# lcd13264-module.net
KiCad netlist of a schematic drawn in EAGLE
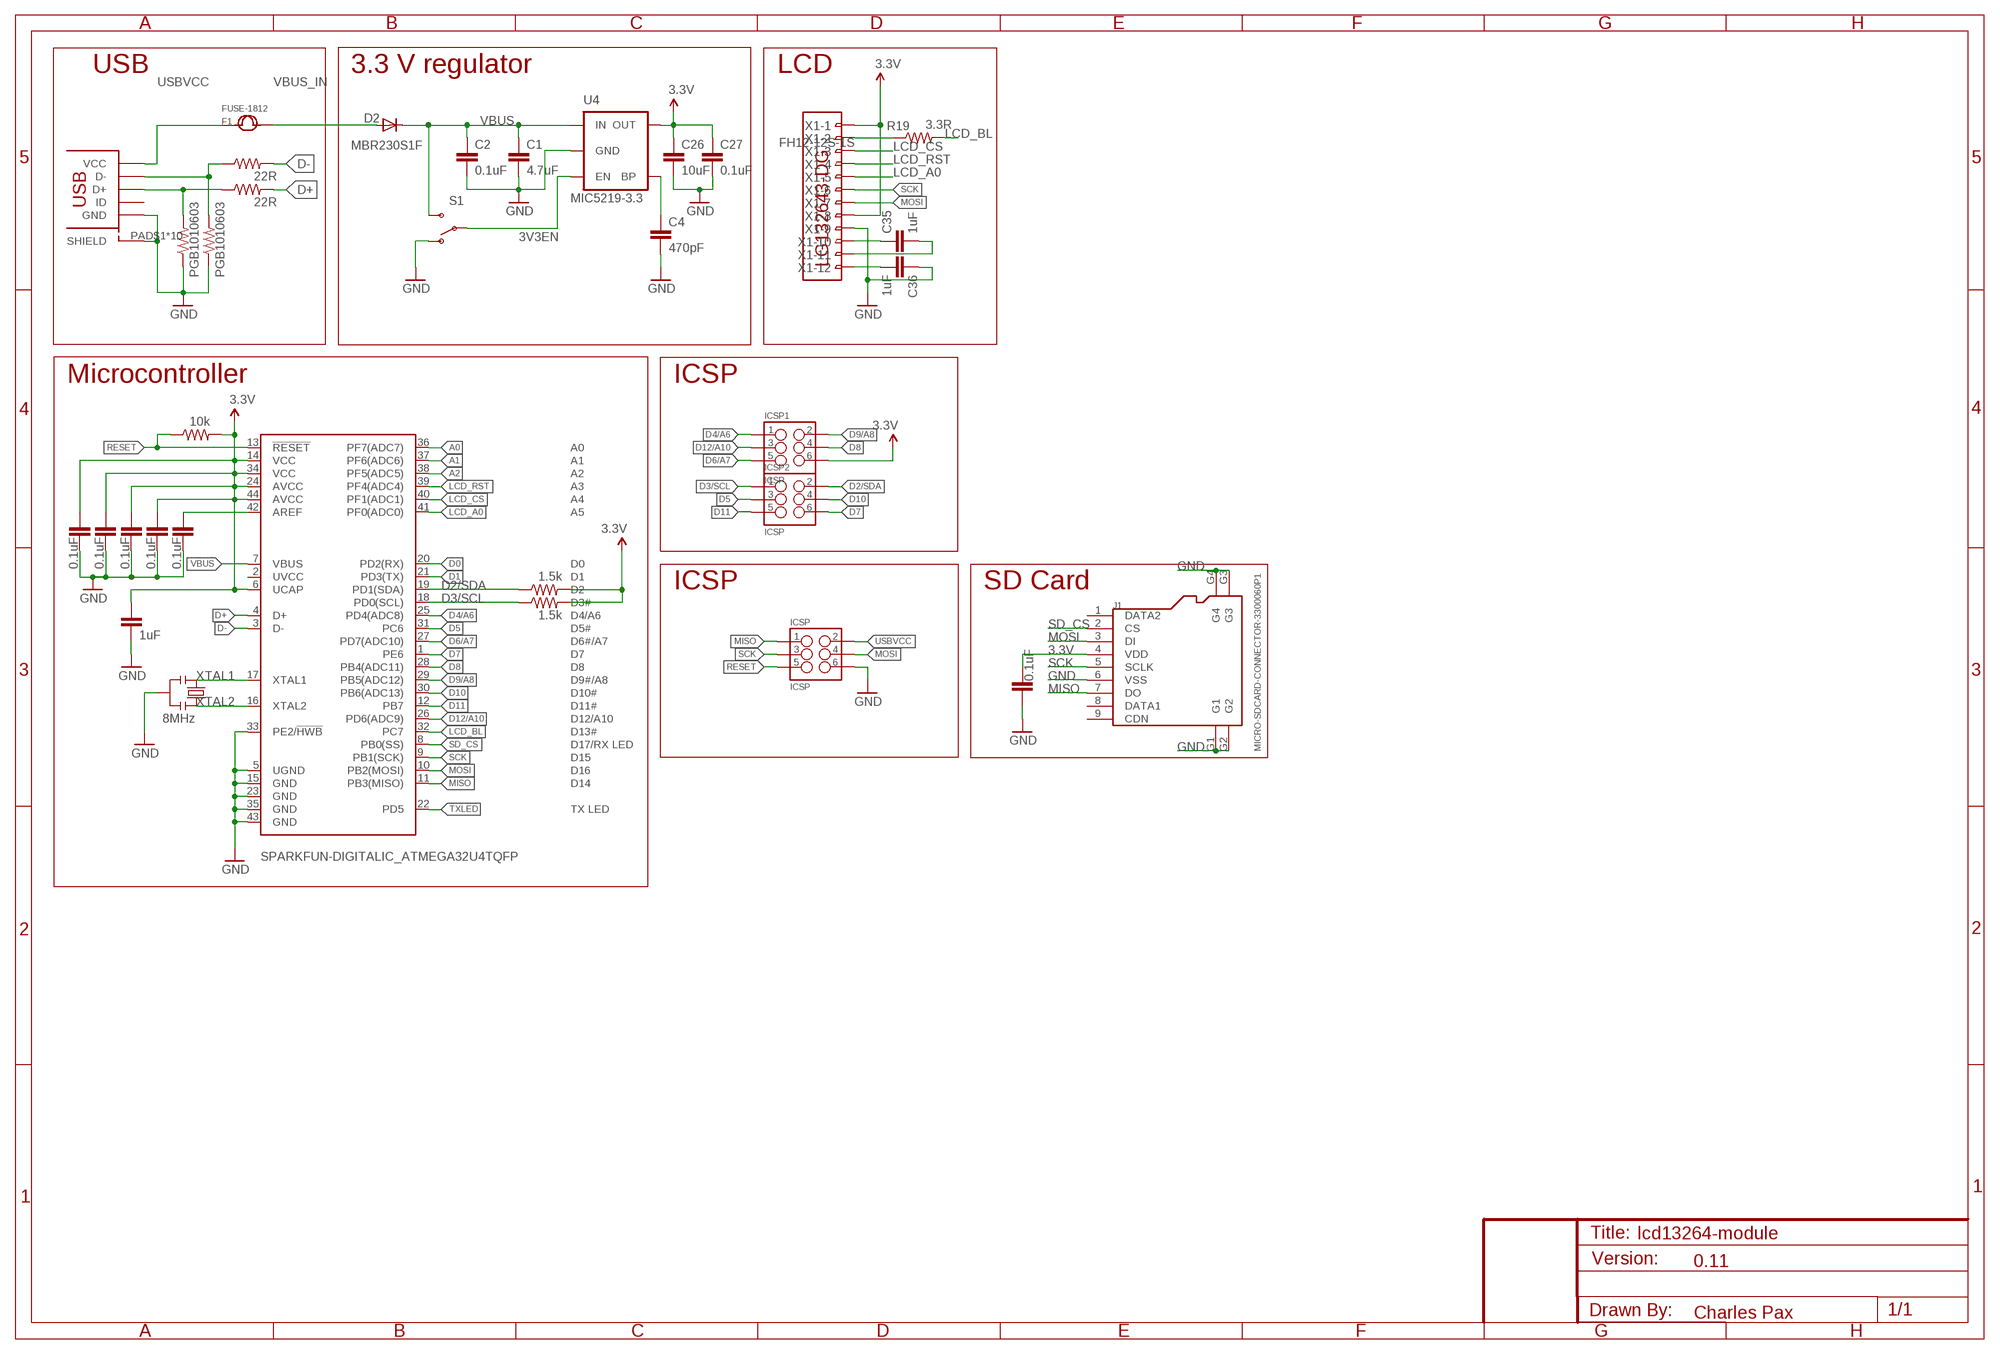
[diagram p0: schematic, sheet 1]

(export (version "E")
  (design (tool "Eeschema 10.0.6"))
  (components
    (comp (ref "C1")
      (value "4.7uF")
      (footprint "eagle-import:SPARKFUN-CAPACITORS_0603-CAP")
      (fields (field (name "MPN") "GRM188R60J475KE19D"))
      (libsource (lib "eagle-import") (part "SPARKFUN-CAPACITORS_CAP0603-CAP"))
    )
    (comp (ref "C2")
      (value "0.1uF")
      (footprint "eagle-import:SPARKFUN-CAPACITORS_0603-CAP")
      (fields (field (name "MPN") "CL10B104KO8NNNC"))
      (libsource (lib "eagle-import") (part "SPARKFUN-CAPACITORS_CAP0603-CAP"))
    )
    (comp (ref "C3")
      (value "0.1uF")
      (footprint "eagle-import:SPARKFUN-CAPACITORS_0603-CAP")
      (fields (field (name "MPN") "CL10B104KO8NNNC"))
      (libsource (lib "eagle-import") (part "SPARKFUN-CAPACITORS_CAP0603-CAP"))
    )
    (comp (ref "C4")
      (value "470pF")
      (footprint "eagle-import:SPARKFUN-CAPACITORS_0603-CAP")
      (fields (field (name "MPN") "C1608X5R1A474K080AA"))
      (libsource (lib "eagle-import") (part "SPARKFUN-CAPACITORS_CAP0603-CAP"))
    )
    (comp (ref "C5")
      (value "0.1uF")
      (footprint "eagle-import:SPARKFUN-CAPACITORS_0603-CAP")
      (fields (field (name "MPN") "CL10B104KO8NNNC"))
      (libsource (lib "eagle-import") (part "SPARKFUN-CAPACITORS_CAP0603-CAP"))
    )
    (comp (ref "C19")
      (value "1uF")
      (footprint "eagle-import:SPARKFUN-CAPACITORS_0603-CAP")
      (fields (field (name "MPN") "LMK107B7105KA-T"))
      (libsource (lib "eagle-import") (part "SPARKFUN-CAPACITORS_CAP0603-CAP"))
    )
    (comp (ref "C21")
      (value "0.1uF")
      (footprint "eagle-import:SPARKFUN-CAPACITORS_0603-CAP")
      (fields (field (name "MPN") "CL10B104KO8NNNC"))
      (libsource (lib "eagle-import") (part "SPARKFUN-CAPACITORS_CAP0603-CAP"))
    )
    (comp (ref "C26")
      (value "10uF")
      (footprint "eagle-import:SPARKFUN-CAPACITORS_0603-CAP")
      (fields (field (name "MPN") "JMK107ABJ106MAHT"))
      (libsource (lib "eagle-import") (part "SPARKFUN-CAPACITORS_CAP0603-CAP"))
    )
    (comp (ref "C27")
      (value "0.1uF")
      (footprint "eagle-import:SPARKFUN-CAPACITORS_0603-CAP")
      (fields (field (name "MPN") "CL10B104KO8NNNC"))
      (libsource (lib "eagle-import") (part "SPARKFUN-CAPACITORS_CAP0603-CAP"))
    )
    (comp (ref "C32")
      (value "0.1uF")
      (footprint "eagle-import:SPARKFUN-CAPACITORS_0603-CAP")
      (fields (field (name "MPN") "CL10B104KO8NNNC"))
      (libsource (lib "eagle-import") (part "SPARKFUN-CAPACITORS_CAP0603-CAP"))
    )
    (comp (ref "C33")
      (value "0.1uF")
      (footprint "eagle-import:SPARKFUN-CAPACITORS_0603-CAP")
      (fields (field (name "MPN") "CL10B104KO8NNNC"))
      (libsource (lib "eagle-import") (part "SPARKFUN-CAPACITORS_CAP0603-CAP"))
    )
    (comp (ref "C34")
      (value "0.1uF")
      (footprint "eagle-import:SPARKFUN-CAPACITORS_0603-CAP")
      (fields (field (name "MPN") "CL10B104KO8NNNC"))
      (libsource (lib "eagle-import") (part "SPARKFUN-CAPACITORS_CAP0603-CAP"))
    )
    (comp (ref "C35")
      (value "1uF")
      (footprint "eagle-import:SPARKFUN-CAPACITORS_0603-CAP")
      (fields (field (name "MPN") "LMK107B7105KA-T"))
      (libsource (lib "eagle-import") (part "SPARKFUN-CAPACITORS_CAP0603-CAP"))
    )
    (comp (ref "C36")
      (value "1uF")
      (footprint "eagle-import:SPARKFUN-CAPACITORS_0603-CAP")
      (fields (field (name "MPN") "LMK107B7105KA-T"))
      (libsource (lib "eagle-import") (part "SPARKFUN-CAPACITORS_CAP0603-CAP"))
    )
    (comp (ref "D2")
      (value "MBR230S1F")
      (footprint "eagle-import:SOD123")
      (fields (field (name "MPN") "B340A-13-F"))
      (libsource (lib "eagle-import") (part "SPARKFUN-DISCRETESEMI_DIODESOD123SOD123"))
    )
    (comp (ref "F1")
      (value "FUSE-1812")
      (footprint "eagle-import:F1812")
      (libsource (lib "eagle-import") (part "FUSE-1812"))
    )
    (comp (ref "ICSP")
      (value "ICSP")
      (footprint "eagle-import:SPARKFUN-CONNECTORS_2X3_SMT_POSTS_PAXINSTRUMENT")
      (fields (field (name "MPN") "95278-101A06LF"))
      (libsource (lib "eagle-import") (part "SPARKFUN-CONNECTORS_M03X2PAX"))
    )
    (comp (ref "ICSP1")
      (value "ICSP")
      (footprint "eagle-import:SPARKFUN-CONNECTORS_2X3_SMT_POSTS_PAXINSTRUMENT")
      (fields (field (name "MPN") "95278-101A06LF"))
      (libsource (lib "eagle-import") (part "SPARKFUN-CONNECTORS_M03X2PAX"))
    )
    (comp (ref "ICSP2")
      (value "ICSP")
      (footprint "eagle-import:SPARKFUN-CONNECTORS_2X3_SMT_POSTS_PAXINSTRUMENT")
      (fields (field (name "MPN") "95278-101A06LF"))
      (libsource (lib "eagle-import") (part "SPARKFUN-CONNECTORS_M03X2PAX"))
    )
    (comp (ref "J1")
      (value "MICRO-SDCARD-CONNECTOR-3300060P1")
      (footprint "eagle-import:9P-SMD-W-RING")
      (libsource (lib "eagle-import") (part "MICRO-SDCARD-CONNECTOR-3300060P1"))
    )
    (comp (ref "R4")
      (value "10k")
      (footprint "eagle-import:SPARKFUN-RESISTORS_0603-RES")
      (fields (field (name "MPN") "RC1608J103CS"))
      (libsource (lib "eagle-import") (part "SPARKFUN-RESISTORS_RESISTOR0603-RES"))
    )
    (comp (ref "R9")
      (value "22R")
      (footprint "eagle-import:SPARKFUN-RESISTORS_0603-RES")
      (fields (field (name "MPN") "RC0603JR-0722RL"))
      (libsource (lib "eagle-import") (part "SPARKFUN-RESISTORS_RESISTOR0603-RES"))
    )
    (comp (ref "R10")
      (value "22R")
      (footprint "eagle-import:SPARKFUN-RESISTORS_0603-RES")
      (fields (field (name "MPN") "RC0603JR-0722RL"))
      (libsource (lib "eagle-import") (part "SPARKFUN-RESISTORS_RESISTOR0603-RES"))
    )
    (comp (ref "R13")
      (value "1.5k")
      (footprint "eagle-import:SPARKFUN-RESISTORS_0603-RES")
      (fields (field (name "MPN") "RC0603JR-071K5L"))
      (libsource (lib "eagle-import") (part "SPARKFUN-RESISTORS_RESISTOR0603-RES"))
    )
    (comp (ref "R14")
      (value "1.5k")
      (footprint "eagle-import:SPARKFUN-RESISTORS_0603-RES")
      (fields (field (name "MPN") "RC0603JR-071K5L"))
      (libsource (lib "eagle-import") (part "SPARKFUN-RESISTORS_RESISTOR0603-RES"))
    )
    (comp (ref "R19")
      (value "3.3R")
      (footprint "eagle-import:SPARKFUN-RESISTORS_0603-RES")
      (libsource (lib "eagle-import") (part "SPARKFUN-RESISTORS_RESISTOR0603-RES"))
    )
    (comp (ref "S1")
      (value "SWITCH-SPDT-SMD-A")
      (footprint "eagle-import:SWITCH-SPST-SMD-A")
      (libsource (lib "eagle-import") (part "SWITCH-SPDT-SMD-A"))
    )
    (comp (ref "U$1")
      (value "USB_MICROSMT+THRUHULE")
      (footprint "eagle-import:USB_MICRO_THRUHOLE")
      (fields (field (name "MPN") "10118194-0001LF"))
      (libsource (lib "eagle-import") (part "USB_MICROSMT+THRUHULE"))
    )
    (comp (ref "U$3")
      (value "SPARKFUN-DIGITALIC_ATMEGA32U4TQFP")
      (footprint "eagle-import:SPARKFUN-DIGITALIC_SPARKFUN-DIGITALIC_TQFP44")
      (libsource (lib "eagle-import") (part "SPARKFUN-DIGITALIC_ATMEGA32U4TQFP"))
    )
    (comp (ref "U$5")
      (value "LG132643-DG")
      (footprint "eagle-import:LG132643-DG")
      (fields (field (name "MPN") "LG132643-DW"))
      (libsource (lib "eagle-import") (part "LG132643-DG"))
    )
    (comp (ref "U4")
      (value "MIC5219-3.3V")
      (footprint "eagle-import:SOT23-5")
      (fields (field (name "MPN") "MIC5219-3.3YM5 TR"))
      (libsource (lib "eagle-import") (part "V_REG_LDOSMD"))
    )
    (comp (ref "X1")
      (value "FH12-12S-1S")
      (footprint "eagle-import:FH12-12S-1SH")
      (libsource (lib "eagle-import") (part "FH12-12S-1S"))
    )
    (comp (ref "Y1")
      (value "RESONATORSMD")
      (footprint "eagle-import:RESONATOR-SMD")
      (fields (field (name "MPN") "CSTCE8M00G52-R0"))
      (libsource (lib "eagle-import") (part "RESONATORSMD"))
    )
    (comp (ref "Z1")
      (value "PGB1010603")
      (footprint "eagle-import:SPARKFUN-RESISTORS_0603-RES")
      (fields (field (name "MPN") "PGB1010603NRHF"))
      (libsource (lib "eagle-import") (part "SPARKFUN-RESISTORS_RESISTOR0603-RES"))
    )
    (comp (ref "Z2")
      (value "PGB1010603")
      (footprint "eagle-import:SPARKFUN-RESISTORS_0603-RES")
      (fields (field (name "MPN") "PGB1010603NRHF"))
      (libsource (lib "eagle-import") (part "SPARKFUN-RESISTORS_RESISTOR0603-RES"))
    )
  )
  (nets
    (net (code "1") (name "/3V3EN") (class "Default")
      (node (ref "S1") (pin "2") (pinfunction "P_2") (pintype "passive"))
      (node (ref "U4") (pin "3") (pinfunction "EN_3") (pintype "input"))
    )
    (net (code "2") (name "/VBUS_IN") (class "Default")
      (node (ref "D2") (pin "A") (pinfunction "A_A") (pintype "passive"))
      (node (ref "F1") (pin "2") (pinfunction "2_2") (pintype "bidirectional"))
    )
    (net (code "3") (name "/XTAL1") (class "Default")
      (node (ref "U$3") (pin "17") (pinfunction "XTAL1_17") (pintype "bidirectional"))
      (node (ref "Y1") (pin "1") (pinfunction "1_1") (pintype "passive"))
    )
    (net (code "4") (name "/XTAL2") (class "Default")
      (node (ref "U$3") (pin "16") (pinfunction "XTAL2_16") (pintype "bidirectional"))
      (node (ref "Y1") (pin "3") (pinfunction "3_3") (pintype "passive"))
    )
    (net (code "5") (name "3.3V") (class "Default")
      (node (ref "C19") (pin "1") (pinfunction "1_1") (pintype "passive"))
      (node (ref "C21") (pin "2") (pinfunction "2_2") (pintype "passive"))
      (node (ref "C26") (pin "1") (pinfunction "1_1") (pintype "passive"))
      (node (ref "C27") (pin "1") (pinfunction "1_1") (pintype "passive"))
      (node (ref "C32") (pin "1") (pinfunction "1_1") (pintype "passive"))
      (node (ref "C33") (pin "1") (pinfunction "1_1") (pintype "passive"))
      (node (ref "C34") (pin "1") (pinfunction "1_1") (pintype "passive"))
      (node (ref "C5") (pin "1") (pinfunction "1_1") (pintype "passive"))
      (node (ref "ICSP1") (pin "6") (pinfunction "6_6") (pintype "bidirectional"))
      (node (ref "J1") (pin "4") (pinfunction "VDD_4") (pintype "bidirectional"))
      (node (ref "R13") (pin "2") (pinfunction "2_2") (pintype "passive"))
      (node (ref "R14") (pin "2") (pinfunction "2_2") (pintype "passive"))
      (node (ref "R4") (pin "2") (pinfunction "2_2") (pintype "passive"))
      (node (ref "U$3") (pin "14") (pinfunction "VCC_14") (pintype "bidirectional"))
      (node (ref "U$3") (pin "24") (pinfunction "AVCC_24") (pintype "bidirectional"))
      (node (ref "U$3") (pin "34") (pinfunction "VCC_34") (pintype "bidirectional"))
      (node (ref "U$3") (pin "44") (pinfunction "AVCC_44") (pintype "bidirectional"))
      (node (ref "U$3") (pin "6") (pinfunction "UCAP_6") (pintype "bidirectional"))
      (node (ref "U4") (pin "5") (pinfunction "OUT_5") (pintype "passive"))
      (node (ref "X1") (pin "1") (pinfunction "1_1") (pintype "passive"))
      (node (ref "X1") (pin "8") (pinfunction "1_8") (pintype "passive"))
    )
    (net (code "6") (name "A0") (class "Default")
      (node (ref "U$3") (pin "36") (pinfunction "PF7(ADC7)_36") (pintype "bidirectional"))
    )
    (net (code "7") (name "A1") (class "Default")
      (node (ref "U$3") (pin "37") (pinfunction "PF6(ADC6)_37") (pintype "bidirectional"))
    )
    (net (code "8") (name "A2") (class "Default")
      (node (ref "U$3") (pin "38") (pinfunction "PF5(ADC5)_38") (pintype "bidirectional"))
    )
    (net (code "9") (name "D+") (class "Default")
      (node (ref "R9") (pin "2") (pinfunction "2_2") (pintype "passive"))
      (node (ref "U$3") (pin "4") (pinfunction "D+_4") (pintype "bidirectional"))
    )
    (net (code "10") (name "D-") (class "Default")
      (node (ref "R10") (pin "2") (pinfunction "2_2") (pintype "passive"))
      (node (ref "U$3") (pin "3") (pinfunction "D-_3") (pintype "bidirectional"))
    )
    (net (code "11") (name "D0") (class "Default")
      (node (ref "U$3") (pin "20") (pinfunction "PD2(RX)_20") (pintype "bidirectional"))
    )
    (net (code "12") (name "D1") (class "Default")
      (node (ref "U$3") (pin "21") (pinfunction "PD3(TX)_21") (pintype "bidirectional"))
    )
    (net (code "13") (name "D2{slash}SDA") (class "Default")
      (node (ref "ICSP2") (pin "2") (pinfunction "2_2") (pintype "bidirectional"))
      (node (ref "R13") (pin "1") (pinfunction "1_1") (pintype "passive"))
      (node (ref "U$3") (pin "19") (pinfunction "PD1(SDA)_19") (pintype "bidirectional"))
    )
    (net (code "14") (name "D3{slash}SCL") (class "Default")
      (node (ref "ICSP2") (pin "1") (pinfunction "1_1") (pintype "bidirectional"))
      (node (ref "R14") (pin "1") (pinfunction "1_1") (pintype "passive"))
      (node (ref "U$3") (pin "18") (pinfunction "PD0(SCL)_18") (pintype "bidirectional"))
    )
    (net (code "15") (name "D4{slash}A6") (class "Default")
      (node (ref "ICSP1") (pin "1") (pinfunction "1_1") (pintype "bidirectional"))
      (node (ref "U$3") (pin "25") (pinfunction "PD4(ADC8)_25") (pintype "bidirectional"))
    )
    (net (code "16") (name "D5") (class "Default")
      (node (ref "ICSP2") (pin "3") (pinfunction "3_3") (pintype "bidirectional"))
      (node (ref "U$3") (pin "31") (pinfunction "PC6_31") (pintype "bidirectional"))
    )
    (net (code "17") (name "D6{slash}A7") (class "Default")
      (node (ref "ICSP1") (pin "5") (pinfunction "5_5") (pintype "bidirectional"))
      (node (ref "U$3") (pin "27") (pinfunction "PD7(ADC10)_27") (pintype "bidirectional"))
    )
    (net (code "18") (name "D7") (class "Default")
      (node (ref "ICSP2") (pin "6") (pinfunction "6_6") (pintype "bidirectional"))
      (node (ref "U$3") (pin "1") (pinfunction "PE6_1") (pintype "bidirectional"))
    )
    (net (code "19") (name "D8") (class "Default")
      (node (ref "ICSP1") (pin "4") (pinfunction "4_4") (pintype "bidirectional"))
      (node (ref "U$3") (pin "28") (pinfunction "PB4(ADC11)_28") (pintype "bidirectional"))
    )
    (net (code "20") (name "D9{slash}A8") (class "Default")
      (node (ref "ICSP1") (pin "2") (pinfunction "2_2") (pintype "bidirectional"))
      (node (ref "U$3") (pin "29") (pinfunction "PB5(ADC12)_29") (pintype "bidirectional"))
    )
    (net (code "21") (name "D10") (class "Default")
      (node (ref "ICSP2") (pin "4") (pinfunction "4_4") (pintype "bidirectional"))
      (node (ref "U$3") (pin "30") (pinfunction "PB6(ADC13)_30") (pintype "bidirectional"))
    )
    (net (code "22") (name "D11") (class "Default")
      (node (ref "ICSP2") (pin "5") (pinfunction "5_5") (pintype "bidirectional"))
      (node (ref "U$3") (pin "12") (pinfunction "PB7_12") (pintype "bidirectional"))
    )
    (net (code "23") (name "D12{slash}A10") (class "Default")
      (node (ref "ICSP1") (pin "3") (pinfunction "3_3") (pintype "bidirectional"))
      (node (ref "U$3") (pin "26") (pinfunction "PD6(ADC9)_26") (pintype "bidirectional"))
    )
    (net (code "24") (name "GND") (class "Default")
      (node (ref "C1") (pin "2") (pinfunction "2_2") (pintype "passive"))
      (node (ref "C19") (pin "2") (pinfunction "2_2") (pintype "passive"))
      (node (ref "C2") (pin "2") (pinfunction "2_2") (pintype "passive"))
      (node (ref "C21") (pin "1") (pinfunction "1_1") (pintype "passive"))
      (node (ref "C26") (pin "2") (pinfunction "2_2") (pintype "passive"))
      (node (ref "C27") (pin "2") (pinfunction "2_2") (pintype "passive"))
      (node (ref "C3") (pin "2") (pinfunction "2_2") (pintype "passive"))
      (node (ref "C32") (pin "2") (pinfunction "2_2") (pintype "passive"))
      (node (ref "C33") (pin "2") (pinfunction "2_2") (pintype "passive"))
      (node (ref "C34") (pin "2") (pinfunction "2_2") (pintype "passive"))
      (node (ref "C36") (pin "1") (pinfunction "1_1") (pintype "passive"))
      (node (ref "C4") (pin "2") (pinfunction "2_2") (pintype "passive"))
      (node (ref "C5") (pin "2") (pinfunction "2_2") (pintype "passive"))
      (node (ref "ICSP") (pin "6") (pinfunction "6_6") (pintype "bidirectional"))
      (node (ref "J1") (pin "6") (pinfunction "VSS_6") (pintype "bidirectional"))
      (node (ref "J1") (pin "G1") (pinfunction "G1_G1") (pintype "bidirectional"))
      (node (ref "J1") (pin "G2") (pinfunction "G2_G2") (pintype "bidirectional"))
      (node (ref "J1") (pin "G3") (pinfunction "G3_G3") (pintype "bidirectional"))
      (node (ref "J1") (pin "G4") (pinfunction "G4_G4") (pintype "bidirectional"))
      (node (ref "S1") (pin "1") (pinfunction "O_1") (pintype "passive"))
      (node (ref "U$1") (pin "PAD$1") (pinfunction "SHIELD_PAD$1") (pintype "bidirectional"))
      (node (ref "U$1") (pin "PAD$10") (pinfunction "SHIELD_PAD$10") (pintype "bidirectional"))
      (node (ref "U$1") (pin "PAD$2") (pinfunction "SHIELD_PAD$2") (pintype "bidirectional"))
      (node (ref "U$1") (pin "PAD$3") (pinfunction "SHIELD_PAD$3") (pintype "bidirectional"))
      (node (ref "U$1") (pin "PAD$4") (pinfunction "SHIELD_PAD$4") (pintype "bidirectional"))
      (node (ref "U$1") (pin "PAD$5") (pinfunction "SHIELD_PAD$5") (pintype "bidirectional"))
      (node (ref "U$1") (pin "PAD$6") (pinfunction "SHIELD_PAD$6") (pintype "bidirectional"))
      (node (ref "U$1") (pin "PAD$7") (pinfunction "SHIELD_PAD$7") (pintype "bidirectional"))
      (node (ref "U$1") (pin "PAD$8") (pinfunction "SHIELD_PAD$8") (pintype "bidirectional"))
      (node (ref "U$1") (pin "PAD$9") (pinfunction "SHIELD_PAD$9") (pintype "bidirectional"))
      (node (ref "U$1") (pin "PIN$5") (pinfunction "GND_PIN$5") (pintype "bidirectional"))
      (node (ref "U$3") (pin "15") (pinfunction "GND_15") (pintype "bidirectional"))
      (node (ref "U$3") (pin "23") (pinfunction "GND_23") (pintype "bidirectional"))
      (node (ref "U$3") (pin "33") (pinfunction "PE2/~{HWB}_33") (pintype "bidirectional"))
      (node (ref "U$3") (pin "35") (pinfunction "GND_35") (pintype "bidirectional"))
      (node (ref "U$3") (pin "43") (pinfunction "GND_43") (pintype "bidirectional"))
      (node (ref "U$3") (pin "5") (pinfunction "UGND_5") (pintype "bidirectional"))
      (node (ref "U4") (pin "2") (pinfunction "GND_2") (pintype "input"))
      (node (ref "X1") (pin "9") (pinfunction "1_9") (pintype "passive"))
      (node (ref "Y1") (pin "2") (pinfunction "2_2") (pintype "passive"))
      (node (ref "Z1") (pin "1") (pinfunction "1_1") (pintype "passive"))
      (node (ref "Z2") (pin "1") (pinfunction "1_1") (pintype "passive"))
    )
    (net (code "25") (name "LCD_A0") (class "Default")
      (node (ref "U$3") (pin "41") (pinfunction "PF0(ADC0)_41") (pintype "bidirectional"))
      (node (ref "X1") (pin "5") (pinfunction "1_5") (pintype "passive"))
    )
    (net (code "26") (name "LCD_BL") (class "Default")
      (node (ref "R19") (pin "2") (pinfunction "2_2") (pintype "passive"))
      (node (ref "U$3") (pin "32") (pinfunction "PC7_32") (pintype "bidirectional"))
    )
    (net (code "27") (name "LCD_CS") (class "Default")
      (node (ref "U$3") (pin "40") (pinfunction "PF1(ADC1)_40") (pintype "bidirectional"))
      (node (ref "X1") (pin "3") (pinfunction "1_3") (pintype "passive"))
    )
    (net (code "28") (name "LCD_RST") (class "Default")
      (node (ref "U$3") (pin "39") (pinfunction "PF4(ADC4)_39") (pintype "bidirectional"))
      (node (ref "X1") (pin "4") (pinfunction "1_4") (pintype "passive"))
    )
    (net (code "29") (name "MISO") (class "Default")
      (node (ref "ICSP") (pin "1") (pinfunction "1_1") (pintype "bidirectional"))
      (node (ref "J1") (pin "7") (pinfunction "DO_7") (pintype "bidirectional"))
      (node (ref "U$3") (pin "11") (pinfunction "PB3(MISO)_11") (pintype "bidirectional"))
    )
    (net (code "30") (name "MOSI") (class "Default")
      (node (ref "ICSP") (pin "4") (pinfunction "4_4") (pintype "bidirectional"))
      (node (ref "J1") (pin "3") (pinfunction "DI_3") (pintype "bidirectional"))
      (node (ref "U$3") (pin "10") (pinfunction "PB2(MOSI)_10") (pintype "bidirectional"))
      (node (ref "X1") (pin "7") (pinfunction "1_7") (pintype "passive"))
    )
    (net (code "31") (name "Net-(U$1-D+)") (class "Default")
      (node (ref "R9") (pin "1") (pinfunction "1_1") (pintype "passive"))
      (node (ref "U$1") (pin "PIN$3") (pinfunction "D+_PIN$3") (pintype "bidirectional"))
      (node (ref "Z1") (pin "2") (pinfunction "2_2") (pintype "passive"))
    )
    (net (code "32") (name "Net-(U$1-D-)") (class "Default")
      (node (ref "R10") (pin "1") (pinfunction "1_1") (pintype "passive"))
      (node (ref "U$1") (pin "PIN$2") (pinfunction "D-_PIN$2") (pintype "bidirectional"))
      (node (ref "Z2") (pin "2") (pinfunction "2_2") (pintype "passive"))
    )
    (net (code "33") (name "Net-(U$3-AREF)") (class "Default")
      (node (ref "C3") (pin "1") (pinfunction "1_1") (pintype "passive"))
      (node (ref "U$3") (pin "42") (pinfunction "AREF_42") (pintype "bidirectional"))
    )
    (net (code "34") (name "Net-(U4-BP)") (class "Default")
      (node (ref "C4") (pin "1") (pinfunction "1_1") (pintype "passive"))
      (node (ref "U4") (pin "4") (pinfunction "BP_4") (pintype "input"))
    )
    (net (code "35") (name "Net-(X1B-1)") (class "Default")
      (node (ref "C35") (pin "1") (pinfunction "1_1") (pintype "passive"))
      (node (ref "X1") (pin "10") (pinfunction "1_10") (pintype "passive"))
    )
    (net (code "36") (name "Net-(X1C-1)") (class "Default")
      (node (ref "C35") (pin "2") (pinfunction "2_2") (pintype "passive"))
      (node (ref "X1") (pin "11") (pinfunction "1_11") (pintype "passive"))
    )
    (net (code "37") (name "Net-(X1D-1)") (class "Default")
      (node (ref "C36") (pin "2") (pinfunction "2_2") (pintype "passive"))
      (node (ref "X1") (pin "12") (pinfunction "1_12") (pintype "passive"))
    )
    (net (code "38") (name "Net-(X1E-1)") (class "Default")
      (node (ref "R19") (pin "1") (pinfunction "1_1") (pintype "passive"))
      (node (ref "X1") (pin "2") (pinfunction "1_2") (pintype "passive"))
    )
    (net (code "39") (name "RESET") (class "Default")
      (node (ref "ICSP") (pin "5") (pinfunction "5_5") (pintype "bidirectional"))
      (node (ref "R4") (pin "1") (pinfunction "1_1") (pintype "passive"))
      (node (ref "U$3") (pin "13") (pinfunction "~{RESET}_13") (pintype "bidirectional"))
    )
    (net (code "40") (name "SCK") (class "Default")
      (node (ref "ICSP") (pin "3") (pinfunction "3_3") (pintype "bidirectional"))
      (node (ref "J1") (pin "5") (pinfunction "SCLK_5") (pintype "bidirectional"))
      (node (ref "U$3") (pin "9") (pinfunction "PB1(SCK)_9") (pintype "bidirectional"))
      (node (ref "X1") (pin "6") (pinfunction "1_6") (pintype "passive"))
    )
    (net (code "41") (name "SD_CS") (class "Default")
      (node (ref "J1") (pin "2") (pinfunction "CS_2") (pintype "bidirectional"))
      (node (ref "U$3") (pin "8") (pinfunction "PB0(SS)_8") (pintype "bidirectional"))
    )
    (net (code "42") (name "TXLED") (class "Default")
      (node (ref "U$3") (pin "22") (pinfunction "PD5_22") (pintype "bidirectional"))
    )
    (net (code "43") (name "USBVCC") (class "Default")
      (node (ref "F1") (pin "1") (pinfunction "1_1") (pintype "bidirectional"))
      (node (ref "ICSP") (pin "2") (pinfunction "2_2") (pintype "bidirectional"))
      (node (ref "U$1") (pin "PIN$1") (pinfunction "VCC_PIN$1") (pintype "bidirectional"))
    )
    (net (code "44") (name "VBUS") (class "Default")
      (node (ref "C1") (pin "1") (pinfunction "1_1") (pintype "passive"))
      (node (ref "C2") (pin "1") (pinfunction "1_1") (pintype "passive"))
      (node (ref "D2") (pin "C") (pinfunction "C_C") (pintype "passive"))
      (node (ref "S1") (pin "3") (pinfunction "S_3") (pintype "passive"))
      (node (ref "U$3") (pin "7") (pinfunction "VBUS_7") (pintype "bidirectional"))
      (node (ref "U4") (pin "1") (pinfunction "IN_1") (pintype "input"))
    )
    (net (code "45") (name "unconnected-(J1-CDN-Pad9)") (class "Default")
      (node (ref "J1") (pin "9") (pinfunction "CDN_9") (pintype "bidirectional"))
    )
    (net (code "46") (name "unconnected-(J1-DATA1-Pad8)") (class "Default")
      (node (ref "J1") (pin "8") (pinfunction "DATA1_8") (pintype "bidirectional"))
    )
    (net (code "47") (name "unconnected-(J1-DATA2-Pad1)") (class "Default")
      (node (ref "J1") (pin "1") (pinfunction "DATA2_1") (pintype "bidirectional"))
    )
    (net (code "48") (name "unconnected-(U$1-ID-PadPIN$4)") (class "Default")
      (node (ref "U$1") (pin "PIN$4") (pinfunction "ID_PIN$4") (pintype "bidirectional"))
    )
    (net (code "49") (name "unconnected-(U$3-UVCC-Pad2)") (class "Default")
      (node (ref "U$3") (pin "2") (pinfunction "UVCC_2") (pintype "bidirectional"))
    )
  )
)
